# Power_Supply.net
KiCad netlist of a schematic drawn in Altium Designer
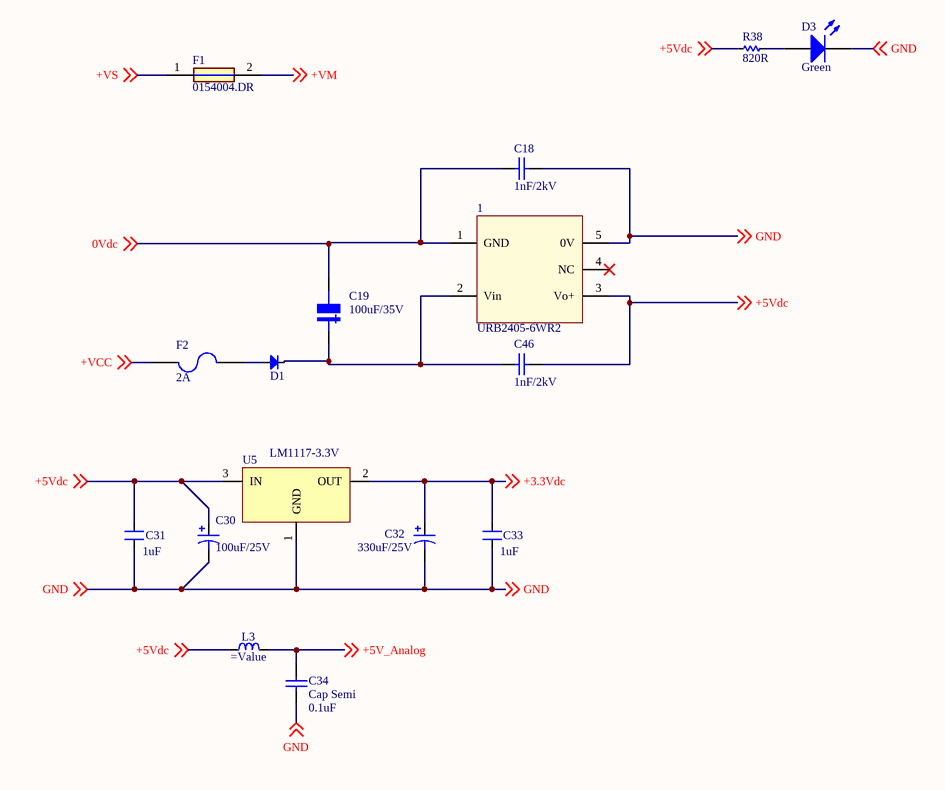
[diagram p0: Power_Supply.SchDoc]

(export (version "E")
  (design (tool "Eeschema 10.0.6"))
  (components
    (comp (ref "1")
      (value "URB2405-6WR2")
      (footprint "URB2405_6WR2")
      (libsource (lib "DCDC") (part "URB2405-6WR2"))
    )
    (comp (ref "C18")
      (value "1nF/2kV")
      (footprint "Cap 3KV 5mm")
      (description "Capacitor")
      (fields (field (name "PUBLISHER") "Altium Limited"))
      (libsource (lib "DoHuong_sch") (part "Cap"))
    )
    (comp (ref "C19")
      (value "100uF/35V")
      (footprint "tu nhom 10 (g)")
      (description "Dán")
      (libsource (lib "Tu dien") (part "Tu Nhom 100uF 35V"))
    )
    (comp (ref "C30")
      (value "100uF/25V")
      (footprint "Cap size C")
      (description "Polarized Capacitor (Axial)")
      (fields (field (name "PUBLISHER") "Altium Limited"))
      (libsource (lib "DoHuong_sch") (part "Cap Pol2"))
    )
    (comp (ref "C31")
      (value "1uF")
      (footprint "Arduino_PLC_PCB:CM-0805 capacitor")
      (description "0805_SMD_20pF")
      (libsource (lib "Arduino_PLC_SchLib") (part "CN"))
    )
    (comp (ref "C32")
      (value "330uF/25V")
      (footprint "Cap size C")
      (description "Polarized Capacitor (Axial)")
      (fields (field (name "PUBLISHER") "Altium Limited"))
      (libsource (lib "DoHuong_sch") (part "Cap Pol2"))
    )
    (comp (ref "C33")
      (value "1uF")
      (footprint "Arduino_PLC_PCB:CM-0805 capacitor")
      (description "0805_SMD_20pF")
      (libsource (lib "Arduino_PLC_SchLib") (part "CN"))
    )
    (comp (ref "C34")
      (value "Cap Semi")
      (footprint "CN-SMD-0805")
      (description "Capacitor (Semiconductor SIM Model)")
      (fields (field (name "ALTIUM_VALUE") "0.1uF") (field (name "PUBLISHER") "Altium Limited"))
      (libsource (lib "Miscellaneous Devices") (part "Cap Semi"))
    )
    (comp (ref "C46")
      (value "1nF/2kV")
      (footprint "Cap 3KV 5mm")
      (description "Capacitor")
      (fields (field (name "PUBLISHER") "Altium Limited"))
      (libsource (lib "DoHuong_sch") (part "Cap"))
    )
    (comp (ref "D1")
      (value "Diode SMD")
      (footprint "DIO-SMD-A")
      (description "Default Diode")
      (fields (field (name "PUBLISHER") "Altium Limited"))
      (libsource (lib "LIBRARY") (part "Diode SMD"))
    )
    (comp (ref "D3")
      (value "Green")
      (footprint "LED-0805-Green")
      (description "Typical RED, GREEN, YELLOW, AMBER GaAs LED")
      (fields (field (name "PUBLISHER") "Altium Limited"))
      (libsource (lib "Miscellaneous Devices") (part "LED2"))
    )
    (comp (ref "F1")
      (value "0154004.DR")
      (footprint "0154001.DRT")
      (description "Fuse")
      (fields (field (name "MOUSER PART NUMBER") "576-0154004.DR"))
      (libsource (lib "SamacSys") (part "0154004.DR"))
    )
    (comp (ref "F2")
      (value "2A")
      (footprint "FUSE_RESETTABLE_SMD_1812")
      (description "Fuse")
      (fields (field (name "PUBLISHER") "Altium Limited"))
      (libsource (lib "DoHuong_sch") (part "Fuse 2"))
    )
    (comp (ref "L3")
      (value "~")
      (footprint "RES 1206")
      (description "Inductor")
      (libsource (lib "DoHuong_sch") (part "Inductor"))
    )
    (comp (ref "R38")
      (value "820R")
      (footprint "RES-SMD-0805")
      (description "Resistor")
      (fields
        (field (name "MANUFACTURER") "Generic Components")
        (field (name "PUBLISHER") "Altium Hobart Technology Centre")
      )
      (libsource (lib "LIBRARY") (part "Res-SMD"))
    )
    (comp (ref "U5")
      (value "LM1117-3.3V")
      (footprint "SOT223")
      (description "800mA Low-Dropout Linear Regulator")
      (fields (field (name "CREATOR") "Nguyen Ba Bien"))
      (libsource (lib "LIBRARY") (part "LM1117"))
    )
  )
  (nets
    (net (code "1") (name "+3.3Vdc") (class "Default")
      (node (ref "C32") (pin "1") (pinfunction "1_1") (pintype "passive"))
      (node (ref "C33") (pin "1") (pinfunction "1_1") (pintype "passive"))
      (node (ref "U5") (pin "2") (pinfunction "OUT_2") (pintype "passive"))
    )
    (net (code "2") (name "+5V_Analog") (class "Default")
      (node (ref "C34") (pin "1") (pinfunction "1_1") (pintype "passive"))
      (node (ref "L3") (pin "2") (pinfunction "2_2") (pintype "passive"))
    )
    (net (code "3") (name "+5Vdc") (class "Default")
      (node (ref "1") (pin "3") (pinfunction "Vo+_3") (pintype "passive"))
      (node (ref "C30") (pin "1") (pinfunction "1_1") (pintype "passive"))
      (node (ref "C31") (pin "1") (pinfunction "1_1") (pintype "passive"))
      (node (ref "C46") (pin "2") (pinfunction "2_2") (pintype "passive"))
      (node (ref "L3") (pin "1") (pinfunction "1_1") (pintype "passive"))
      (node (ref "R38") (pin "1") (pinfunction "1_1") (pintype "passive"))
      (node (ref "U5") (pin "3") (pinfunction "IN_3") (pintype "passive"))
    )
    (net (code "4") (name "+VCC") (class "Default")
      (node (ref "F2") (pin "1") (pinfunction "1_1") (pintype "passive"))
    )
    (net (code "5") (name "+VM") (class "Default")
      (node (ref "F1") (pin "2") (pinfunction "2_2") (pintype "passive"))
    )
    (net (code "6") (name "+VS") (class "Default")
      (node (ref "F1") (pin "1") (pinfunction "1_1") (pintype "passive"))
    )
    (net (code "7") (name "0Vdc") (class "Default")
      (node (ref "1") (pin "1") (pinfunction "GND_1") (pintype "passive"))
      (node (ref "C18") (pin "1") (pinfunction "1_1") (pintype "passive"))
      (node (ref "C19") (pin "2") (pinfunction "2_2") (pintype "passive"))
    )
    (net (code "8") (name "GND") (class "Default")
      (node (ref "1") (pin "5") (pinfunction "0V_5") (pintype "passive"))
      (node (ref "C18") (pin "2") (pinfunction "2_2") (pintype "passive"))
      (node (ref "C30") (pin "2") (pinfunction "2_2") (pintype "passive"))
      (node (ref "C31") (pin "2") (pinfunction "2_2") (pintype "passive"))
      (node (ref "C32") (pin "2") (pinfunction "2_2") (pintype "passive"))
      (node (ref "C33") (pin "2") (pinfunction "2_2") (pintype "passive"))
      (node (ref "C34") (pin "2") (pinfunction "2_2") (pintype "passive"))
      (node (ref "D3") (pin "2") (pinfunction "K_2") (pintype "passive"))
      (node (ref "U5") (pin "1") (pinfunction "GND_1") (pintype "passive"))
    )
    (net (code "9") (name "Net-(1-Vin)") (class "Default")
      (node (ref "1") (pin "2") (pinfunction "Vin_2") (pintype "passive"))
      (node (ref "C19") (pin "1") (pinfunction "1_1") (pintype "passive"))
      (node (ref "C46") (pin "1") (pinfunction "1_1") (pintype "passive"))
      (node (ref "D1") (pin "2") (pinfunction "K_2") (pintype "passive"))
    )
    (net (code "10") (name "Net-(D1-A)") (class "Default")
      (node (ref "D1") (pin "1") (pinfunction "A_1") (pintype "passive"))
      (node (ref "F2") (pin "2") (pinfunction "2_2") (pintype "passive"))
    )
    (net (code "11") (name "Net-(D3-A)") (class "Default")
      (node (ref "D3") (pin "1") (pinfunction "A_1") (pintype "passive"))
      (node (ref "R38") (pin "2") (pinfunction "2_2") (pintype "passive"))
    )
    (net (code "12") (name "unconnected-(1-NC-Pad4)") (class "Default")
      (node (ref "1") (pin "4") (pinfunction "NC_4") (pintype "passive+no_connect"))
    )
  )
)
